# 160229_AriloRX_REV3_1_1.net
KiCad netlist of a schematic drawn in EAGLE
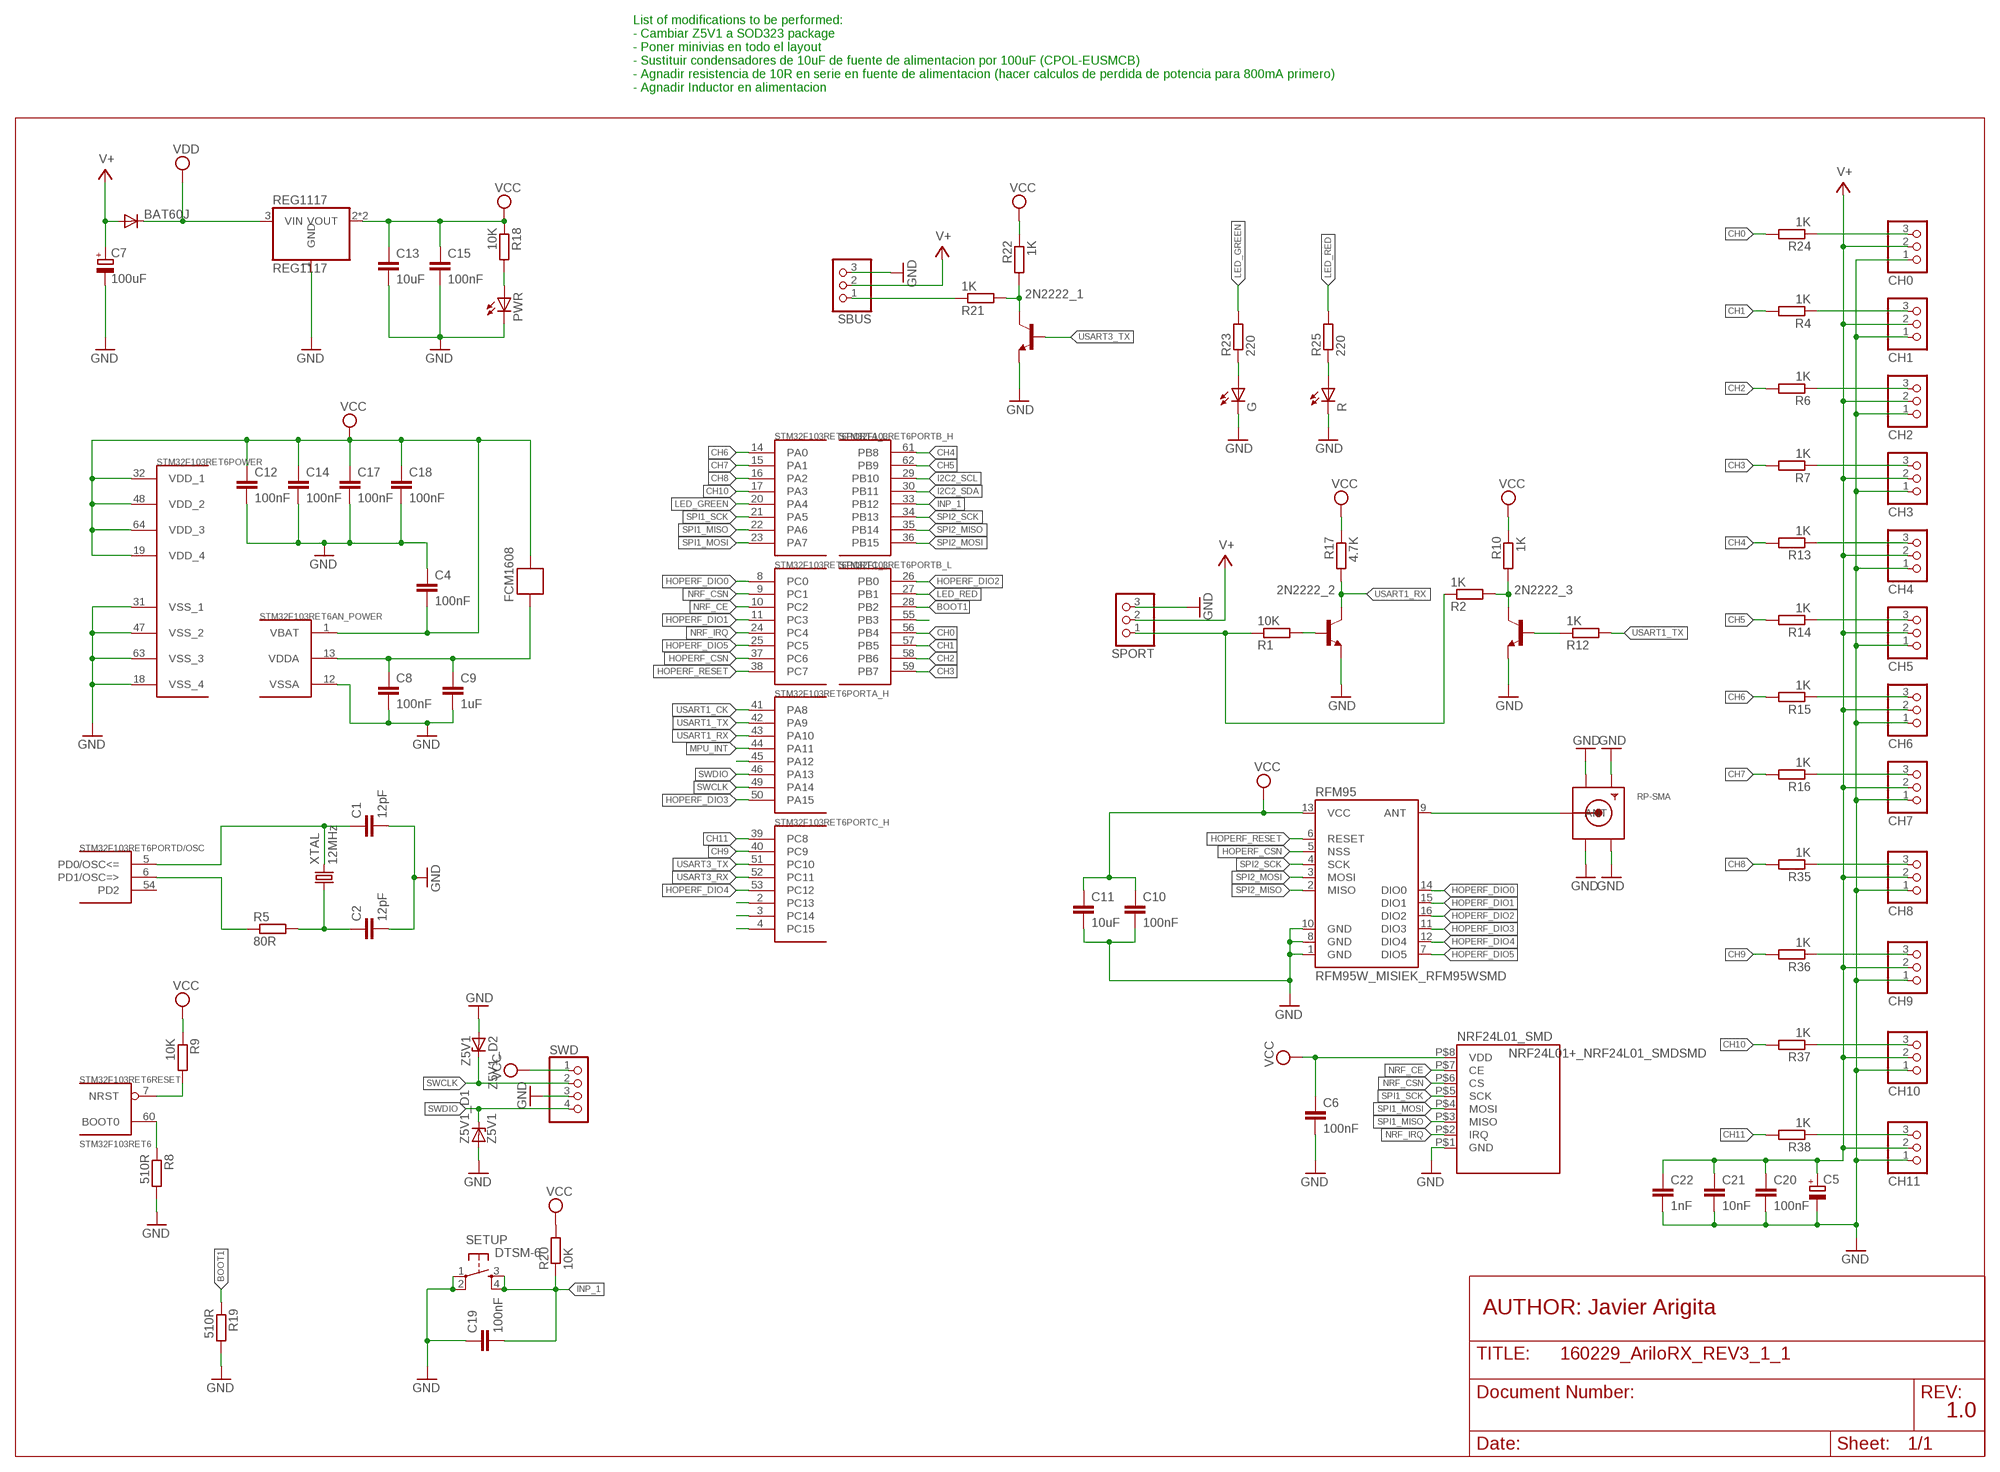
[diagram p0: schematic, sheet 1]

(export (version "E")
  (design (tool "Eeschema 10.0.6"))
  (components
    (comp (ref "2N2222_1")
      (value "MMBT2222ALT1-NPN-SOT23-BEC")
      (footprint "eagle-import:SOT23-BEC")
      (libsource (lib "eagle-import") (part "-NPN-SOT23-BECMMBT2222ALT1"))
    )
    (comp (ref "2N2222_2")
      (value "MMBT2222ALT1-NPN-SOT23-BEC")
      (footprint "eagle-import:SOT23-BEC")
      (libsource (lib "eagle-import") (part "-NPN-SOT23-BECMMBT2222ALT1"))
    )
    (comp (ref "2N2222_3")
      (value "MMBT2222ALT1-NPN-SOT23-BEC")
      (footprint "eagle-import:SOT23-BEC")
      (libsource (lib "eagle-import") (part "-NPN-SOT23-BECMMBT2222ALT1"))
    )
    (comp (ref "BAT60J")
      (value "DIODE-SOD323-R")
      (footprint "eagle-import:SOD323-R")
      (libsource (lib "eagle-import") (part "DIODE-SOD323-R"))
    )
    (comp (ref "C1")
      (value "12pF")
      (footprint "eagle-import:RESISTOR_C0603")
      (libsource (lib "eagle-import") (part "RESISTOR_C-EUC0603"))
    )
    (comp (ref "C2")
      (value "12pF")
      (footprint "eagle-import:RESISTOR_C0603")
      (libsource (lib "eagle-import") (part "RESISTOR_C-EUC0603"))
    )
    (comp (ref "C4")
      (value "100nF")
      (footprint "eagle-import:RESISTOR_C0603")
      (libsource (lib "eagle-import") (part "RESISTOR_C-EUC0603"))
    )
    (comp (ref "C5")
      (value "CPOL-EUSMCB")
      (footprint "eagle-import:SMC_B")
      (libsource (lib "eagle-import") (part "CPOL-EUSMCB"))
    )
    (comp (ref "C6")
      (value "100nF")
      (footprint "eagle-import:RESISTOR_C0603")
      (libsource (lib "eagle-import") (part "RESISTOR_C-EUC0603"))
    )
    (comp (ref "C7")
      (value "100uF")
      (footprint "eagle-import:SMC_B")
      (libsource (lib "eagle-import") (part "CPOL-EUSMCB"))
    )
    (comp (ref "C8")
      (value "100nF")
      (footprint "eagle-import:RESISTOR_C0603")
      (libsource (lib "eagle-import") (part "RESISTOR_C-EUC0603"))
    )
    (comp (ref "C9")
      (value "1uF")
      (footprint "eagle-import:RESISTOR_C0603")
      (libsource (lib "eagle-import") (part "RESISTOR_C-EUC0603"))
    )
    (comp (ref "C10")
      (value "100nF")
      (footprint "eagle-import:RESISTOR_C0603")
      (libsource (lib "eagle-import") (part "RESISTOR_C-EUC0603"))
    )
    (comp (ref "C11")
      (value "10uF")
      (footprint "eagle-import:RESISTOR_C3216")
      (libsource (lib "eagle-import") (part "RESISTOR_C-EUC3216"))
    )
    (comp (ref "C12")
      (value "100nF")
      (footprint "eagle-import:RESISTOR_C0603")
      (libsource (lib "eagle-import") (part "RESISTOR_C-EUC0603"))
    )
    (comp (ref "C13")
      (value "10uF")
      (footprint "eagle-import:RESISTOR_C3216")
      (libsource (lib "eagle-import") (part "RESISTOR_C-EUC3216"))
    )
    (comp (ref "C14")
      (value "100nF")
      (footprint "eagle-import:RESISTOR_C0603")
      (libsource (lib "eagle-import") (part "RESISTOR_C-EUC0603"))
    )
    (comp (ref "C15")
      (value "100nF")
      (footprint "eagle-import:RESISTOR_C0603")
      (libsource (lib "eagle-import") (part "RESISTOR_C-EUC0603"))
    )
    (comp (ref "C17")
      (value "100nF")
      (footprint "eagle-import:RESISTOR_C0603")
      (libsource (lib "eagle-import") (part "RESISTOR_C-EUC0603"))
    )
    (comp (ref "C18")
      (value "100nF")
      (footprint "eagle-import:RESISTOR_C0603")
      (libsource (lib "eagle-import") (part "RESISTOR_C-EUC0603"))
    )
    (comp (ref "C19")
      (value "100nF")
      (footprint "eagle-import:RESISTOR_C0603")
      (libsource (lib "eagle-import") (part "RESISTOR_C-EUC0603"))
    )
    (comp (ref "C20")
      (value "100nF")
      (footprint "eagle-import:RESISTOR_C0603")
      (libsource (lib "eagle-import") (part "RESISTOR_C-EUC0603"))
    )
    (comp (ref "C21")
      (value "10nF")
      (footprint "eagle-import:RESISTOR_C0603")
      (libsource (lib "eagle-import") (part "RESISTOR_C-EUC0603"))
    )
    (comp (ref "C22")
      (value "1nF")
      (footprint "eagle-import:RESISTOR_C0603")
      (libsource (lib "eagle-import") (part "RESISTOR_C-EUC0603"))
    )
    (comp (ref "CH0")
      (value "PINHD-1X3")
      (footprint "eagle-import:1X03")
      (libsource (lib "eagle-import") (part "PINHD-1X3"))
    )
    (comp (ref "CH1")
      (value "PINHD-1X3")
      (footprint "eagle-import:1X03")
      (libsource (lib "eagle-import") (part "PINHD-1X3"))
    )
    (comp (ref "CH2")
      (value "PINHD-1X3")
      (footprint "eagle-import:1X03")
      (libsource (lib "eagle-import") (part "PINHD-1X3"))
    )
    (comp (ref "CH3")
      (value "PINHD-1X3")
      (footprint "eagle-import:1X03")
      (libsource (lib "eagle-import") (part "PINHD-1X3"))
    )
    (comp (ref "CH4")
      (value "PINHD-1X3")
      (footprint "eagle-import:1X03")
      (libsource (lib "eagle-import") (part "PINHD-1X3"))
    )
    (comp (ref "CH5")
      (value "PINHD-1X3")
      (footprint "eagle-import:1X03")
      (libsource (lib "eagle-import") (part "PINHD-1X3"))
    )
    (comp (ref "CH6")
      (value "PINHD-1X3")
      (footprint "eagle-import:1X03")
      (libsource (lib "eagle-import") (part "PINHD-1X3"))
    )
    (comp (ref "CH7")
      (value "PINHD-1X3")
      (footprint "eagle-import:1X03")
      (libsource (lib "eagle-import") (part "PINHD-1X3"))
    )
    (comp (ref "CH8")
      (value "PINHD-1X3")
      (footprint "eagle-import:1X03")
      (libsource (lib "eagle-import") (part "PINHD-1X3"))
    )
    (comp (ref "CH9")
      (value "PINHD-1X3")
      (footprint "eagle-import:1X03")
      (libsource (lib "eagle-import") (part "PINHD-1X3"))
    )
    (comp (ref "CH10")
      (value "PINHD-1X3")
      (footprint "eagle-import:1X03")
      (libsource (lib "eagle-import") (part "PINHD-1X3"))
    )
    (comp (ref "CH11")
      (value "PINHD-1X3")
      (footprint "eagle-import:1X03")
      (libsource (lib "eagle-import") (part "PINHD-1X3"))
    )
    (comp (ref "FCM1608")
      (value "FERRITE-BEAD")
      (footprint "eagle-import:R0603")
      (libsource (lib "eagle-import") (part "FERRITE-BEAD"))
    )
    (comp (ref "G")
      (value "LEDCHIP-LED0603")
      (footprint "eagle-import:CHIP-LED0603")
      (libsource (lib "eagle-import") (part "LEDCHIP-LED0603"))
    )
    (comp (ref "NRF24L01_SMD")
      (value "NRF24L01+_NRF24L01_SMDSMD")
      (footprint "eagle-import:NRF24L01+_NRF24L01_SMD")
      (libsource (lib "eagle-import") (part "NRF24L01+_NRF24L01_SMDSMD"))
    )
    (comp (ref "PWR")
      (value "LED_LEDCHIP-LED0603")
      (footprint "eagle-import:LED_CHIP-LED0603")
      (libsource (lib "eagle-import") (part "LED_LEDCHIP-LED0603"))
    )
    (comp (ref "R")
      (value "LEDCHIP-LED0603")
      (footprint "eagle-import:CHIP-LED0603")
      (libsource (lib "eagle-import") (part "LEDCHIP-LED0603"))
    )
    (comp (ref "R1")
      (value "10K")
      (footprint "eagle-import:RCL_R0603")
      (libsource (lib "eagle-import") (part "RCL_R-EU_R0603"))
    )
    (comp (ref "R2")
      (value "1K")
      (footprint "eagle-import:RCL_R0603")
      (libsource (lib "eagle-import") (part "RCL_R-EU_R0603"))
    )
    (comp (ref "R4")
      (value "1K")
      (footprint "eagle-import:RCL_R0603")
      (libsource (lib "eagle-import") (part "RCL_R-EU_R0603"))
    )
    (comp (ref "R5")
      (value "80R")
      (footprint "eagle-import:RCL_R0603")
      (libsource (lib "eagle-import") (part "RCL_R-EU_R0603"))
    )
    (comp (ref "R6")
      (value "1K")
      (footprint "eagle-import:RCL_R0603")
      (libsource (lib "eagle-import") (part "RCL_R-EU_R0603"))
    )
    (comp (ref "R7")
      (value "1K")
      (footprint "eagle-import:RCL_R0603")
      (libsource (lib "eagle-import") (part "RCL_R-EU_R0603"))
    )
    (comp (ref "R8")
      (value "510R")
      (footprint "eagle-import:RCL_R0603")
      (libsource (lib "eagle-import") (part "RCL_R-EU_R0603"))
    )
    (comp (ref "R9")
      (value "10K")
      (footprint "eagle-import:RCL_R0603")
      (libsource (lib "eagle-import") (part "RCL_R-EU_R0603"))
    )
    (comp (ref "R10")
      (value "1K")
      (footprint "eagle-import:RCL_R0603")
      (libsource (lib "eagle-import") (part "RCL_R-EU_R0603"))
    )
    (comp (ref "R12")
      (value "1K")
      (footprint "eagle-import:RCL_R0603")
      (libsource (lib "eagle-import") (part "RCL_R-EU_R0603"))
    )
    (comp (ref "R13")
      (value "1K")
      (footprint "eagle-import:RCL_R0603")
      (libsource (lib "eagle-import") (part "RCL_R-EU_R0603"))
    )
    (comp (ref "R14")
      (value "1K")
      (footprint "eagle-import:RCL_R0603")
      (libsource (lib "eagle-import") (part "RCL_R-EU_R0603"))
    )
    (comp (ref "R15")
      (value "1K")
      (footprint "eagle-import:RCL_R0603")
      (libsource (lib "eagle-import") (part "RCL_R-EU_R0603"))
    )
    (comp (ref "R16")
      (value "1K")
      (footprint "eagle-import:RCL_R0603")
      (libsource (lib "eagle-import") (part "RCL_R-EU_R0603"))
    )
    (comp (ref "R17")
      (value "4.7K")
      (footprint "eagle-import:RCL_R0603")
      (libsource (lib "eagle-import") (part "RCL_R-EU_R0603"))
    )
    (comp (ref "R18")
      (value "10K")
      (footprint "eagle-import:RCL_R0603")
      (libsource (lib "eagle-import") (part "RCL_R-EU_R0603"))
    )
    (comp (ref "R19")
      (value "510R")
      (footprint "eagle-import:RCL_R0603")
      (libsource (lib "eagle-import") (part "RCL_R-EU_R0603"))
    )
    (comp (ref "R20")
      (value "10K")
      (footprint "eagle-import:RCL_R0603")
      (libsource (lib "eagle-import") (part "RCL_R-EU_R0603"))
    )
    (comp (ref "R21")
      (value "1K")
      (footprint "eagle-import:RCL_R0603")
      (libsource (lib "eagle-import") (part "RCL_R-EU_R0603"))
    )
    (comp (ref "R22")
      (value "1K")
      (footprint "eagle-import:RCL_R0603")
      (libsource (lib "eagle-import") (part "RCL_R-EU_R0603"))
    )
    (comp (ref "R23")
      (value "220")
      (footprint "eagle-import:RCL_R0603")
      (libsource (lib "eagle-import") (part "RCL_R-EU_R0603"))
    )
    (comp (ref "R24")
      (value "1K")
      (footprint "eagle-import:RCL_R0603")
      (libsource (lib "eagle-import") (part "RCL_R-EU_R0603"))
    )
    (comp (ref "R25")
      (value "220")
      (footprint "eagle-import:RCL_R0603")
      (libsource (lib "eagle-import") (part "RCL_R-EU_R0603"))
    )
    (comp (ref "R35")
      (value "1K")
      (footprint "eagle-import:RCL_R0603")
      (libsource (lib "eagle-import") (part "RCL_R-EU_R0603"))
    )
    (comp (ref "R36")
      (value "1K")
      (footprint "eagle-import:RCL_R0603")
      (libsource (lib "eagle-import") (part "RCL_R-EU_R0603"))
    )
    (comp (ref "R37")
      (value "1K")
      (footprint "eagle-import:RCL_R0603")
      (libsource (lib "eagle-import") (part "RCL_R-EU_R0603"))
    )
    (comp (ref "R38")
      (value "1K")
      (footprint "eagle-import:RCL_R0603")
      (libsource (lib "eagle-import") (part "RCL_R-EU_R0603"))
    )
    (comp (ref "REG1117")
      (value "REG1117")
      (footprint "eagle-import:SOT223")
      (libsource (lib "eagle-import") (part "REG1117"))
    )
    (comp (ref "RFM95")
      (value "RFM95W_MISIEK_RFM95WSMD")
      (footprint "eagle-import:RFM95W_MISIEK_RFM95W_SMD")
      (libsource (lib "eagle-import") (part "RFM95W_MISIEK_RFM95WSMD"))
    )
    (comp (ref "RP-SMA")
      (value "SMACONNECTOR_EDGE")
      (footprint "eagle-import:SMA_EDGELAUNCH")
      (libsource (lib "eagle-import") (part "SMACONNECTOR_EDGE"))
    )
    (comp (ref "SBUS")
      (value "PINHD-1X3")
      (footprint "eagle-import:1X03")
      (libsource (lib "eagle-import") (part "PINHD-1X3"))
    )
    (comp (ref "SETUP")
      (value "DTSM-6")
      (footprint "eagle-import:DTSM-6")
      (libsource (lib "eagle-import") (part "DTSM-6"))
    )
    (comp (ref "SPORT")
      (value "PINHD-1X3")
      (footprint "eagle-import:1X03")
      (libsource (lib "eagle-import") (part "PINHD-1X3"))
    )
    (comp (ref "STM32F103RET6")
      (value "STM32F103RET6")
      (footprint "eagle-import:TQFP64")
      (libsource (lib "eagle-import") (part "STM32F10XRXT6"))
    )
    (comp (ref "SWD")
      (value "PINHD-1X4")
      (footprint "eagle-import:1X04")
      (libsource (lib "eagle-import") (part "PINHD-1X4"))
    )
    (comp (ref "XTAL")
      (value "12MHz")
      (footprint "eagle-import:CRYSTAL-SMD-5X3")
      (libsource (lib "eagle-import") (part "CRYSTAL5X3"))
    )
    (comp (ref "Z5V1_D1")
      (value "Z5V1")
      (footprint "eagle-import:SOD80C")
      (libsource (lib "eagle-import") (part "ZENER-DIODESOD80C"))
    )
    (comp (ref "Z5V1_D2")
      (value "Z5V1")
      (footprint "eagle-import:SOD80C")
      (libsource (lib "eagle-import") (part "ZENER-DIODESOD80C"))
    )
  )
  (nets
    (net (code "1") (name "BOOT1") (class "Default")
      (node (ref "R19") (pin "1") (pinfunction "1_1") (pintype "passive"))
      (node (ref "STM32F103RET6") (pin "28") (pinfunction "PB2_28") (pintype "bidirectional"))
    )
    (net (code "2") (name "CH0") (class "Default")
      (node (ref "R24") (pin "2") (pinfunction "2_2") (pintype "passive"))
      (node (ref "STM32F103RET6") (pin "56") (pinfunction "PB4_56") (pintype "bidirectional"))
    )
    (net (code "3") (name "CH1") (class "Default")
      (node (ref "R4") (pin "2") (pinfunction "2_2") (pintype "passive"))
      (node (ref "STM32F103RET6") (pin "57") (pinfunction "PB5_57") (pintype "bidirectional"))
    )
    (net (code "4") (name "CH2") (class "Default")
      (node (ref "R6") (pin "2") (pinfunction "2_2") (pintype "passive"))
      (node (ref "STM32F103RET6") (pin "58") (pinfunction "PB6_58") (pintype "bidirectional"))
    )
    (net (code "5") (name "CH3") (class "Default")
      (node (ref "R7") (pin "2") (pinfunction "2_2") (pintype "passive"))
      (node (ref "STM32F103RET6") (pin "59") (pinfunction "PB7_59") (pintype "bidirectional"))
    )
    (net (code "6") (name "CH4") (class "Default")
      (node (ref "R13") (pin "2") (pinfunction "2_2") (pintype "passive"))
      (node (ref "STM32F103RET6") (pin "61") (pinfunction "PB8_61") (pintype "bidirectional"))
    )
    (net (code "7") (name "CH5") (class "Default")
      (node (ref "R14") (pin "2") (pinfunction "2_2") (pintype "passive"))
      (node (ref "STM32F103RET6") (pin "62") (pinfunction "PB9_62") (pintype "bidirectional"))
    )
    (net (code "8") (name "CH6") (class "Default")
      (node (ref "R15") (pin "2") (pinfunction "2_2") (pintype "passive"))
      (node (ref "STM32F103RET6") (pin "14") (pinfunction "PA0_14") (pintype "bidirectional"))
    )
    (net (code "9") (name "CH7") (class "Default")
      (node (ref "R16") (pin "2") (pinfunction "2_2") (pintype "passive"))
      (node (ref "STM32F103RET6") (pin "15") (pinfunction "PA1_15") (pintype "bidirectional"))
    )
    (net (code "10") (name "CH8") (class "Default")
      (node (ref "R35") (pin "2") (pinfunction "2_2") (pintype "passive"))
      (node (ref "STM32F103RET6") (pin "16") (pinfunction "PA2_16") (pintype "bidirectional"))
    )
    (net (code "11") (name "CH9") (class "Default")
      (node (ref "R36") (pin "2") (pinfunction "2_2") (pintype "passive"))
      (node (ref "STM32F103RET6") (pin "40") (pinfunction "PC9_40") (pintype "bidirectional"))
    )
    (net (code "12") (name "CH10") (class "Default")
      (node (ref "R37") (pin "2") (pinfunction "2_2") (pintype "passive"))
      (node (ref "STM32F103RET6") (pin "17") (pinfunction "PA3_17") (pintype "bidirectional"))
    )
    (net (code "13") (name "CH11") (class "Default")
      (node (ref "R38") (pin "2") (pinfunction "2_2") (pintype "passive"))
      (node (ref "STM32F103RET6") (pin "39") (pinfunction "PC8_39") (pintype "bidirectional"))
    )
    (net (code "14") (name "GND") (class "Default")
      (node (ref "2N2222_1") (pin "E") (pinfunction "E_E") (pintype "passive"))
      (node (ref "2N2222_2") (pin "E") (pinfunction "E_E") (pintype "passive"))
      (node (ref "2N2222_3") (pin "E") (pinfunction "E_E") (pintype "passive"))
      (node (ref "C1") (pin "2") (pinfunction "2_2") (pintype "passive"))
      (node (ref "C10") (pin "2") (pinfunction "2_2") (pintype "passive"))
      (node (ref "C11") (pin "2") (pinfunction "2_2") (pintype "passive"))
      (node (ref "C12") (pin "2") (pinfunction "2_2") (pintype "passive"))
      (node (ref "C13") (pin "2") (pinfunction "2_2") (pintype "passive"))
      (node (ref "C14") (pin "2") (pinfunction "2_2") (pintype "passive"))
      (node (ref "C15") (pin "2") (pinfunction "2_2") (pintype "passive"))
      (node (ref "C17") (pin "2") (pinfunction "2_2") (pintype "passive"))
      (node (ref "C18") (pin "2") (pinfunction "2_2") (pintype "passive"))
      (node (ref "C19") (pin "1") (pinfunction "1_1") (pintype "passive"))
      (node (ref "C2") (pin "2") (pinfunction "2_2") (pintype "passive"))
      (node (ref "C20") (pin "2") (pinfunction "2_2") (pintype "passive"))
      (node (ref "C21") (pin "2") (pinfunction "2_2") (pintype "passive"))
      (node (ref "C22") (pin "2") (pinfunction "2_2") (pintype "passive"))
      (node (ref "C4") (pin "1") (pinfunction "1_1") (pintype "passive"))
      (node (ref "C5") (pin "-") (pinfunction "-_-") (pintype "passive"))
      (node (ref "C6") (pin "2") (pinfunction "2_2") (pintype "passive"))
      (node (ref "C7") (pin "-") (pinfunction "-_-") (pintype "passive"))
      (node (ref "C8") (pin "2") (pinfunction "2_2") (pintype "passive"))
      (node (ref "C9") (pin "2") (pinfunction "2_2") (pintype "passive"))
      (node (ref "CH0") (pin "1") (pinfunction "1_1") (pintype "passive"))
      (node (ref "CH1") (pin "1") (pinfunction "1_1") (pintype "passive"))
      (node (ref "CH10") (pin "1") (pinfunction "1_1") (pintype "passive"))
      (node (ref "CH11") (pin "1") (pinfunction "1_1") (pintype "passive"))
      (node (ref "CH2") (pin "1") (pinfunction "1_1") (pintype "passive"))
      (node (ref "CH3") (pin "1") (pinfunction "1_1") (pintype "passive"))
      (node (ref "CH4") (pin "1") (pinfunction "1_1") (pintype "passive"))
      (node (ref "CH5") (pin "1") (pinfunction "1_1") (pintype "passive"))
      (node (ref "CH6") (pin "1") (pinfunction "1_1") (pintype "passive"))
      (node (ref "CH7") (pin "1") (pinfunction "1_1") (pintype "passive"))
      (node (ref "CH8") (pin "1") (pinfunction "1_1") (pintype "passive"))
      (node (ref "CH9") (pin "1") (pinfunction "1_1") (pintype "passive"))
      (node (ref "G") (pin "C") (pinfunction "C_C") (pintype "passive"))
      (node (ref "NRF24L01_SMD") (pin "P$1") (pinfunction "GND_P$1") (pintype "power_in"))
      (node (ref "PWR") (pin "C") (pinfunction "C_C") (pintype "passive"))
      (node (ref "R") (pin "C") (pinfunction "C_C") (pintype "passive"))
      (node (ref "R19") (pin "2") (pinfunction "2_2") (pintype "passive"))
      (node (ref "R8") (pin "2") (pinfunction "2_2") (pintype "passive"))
      (node (ref "REG1117") (pin "1") (pinfunction "GND_1") (pintype "power_in"))
      (node (ref "RFM95") (pin "1") (pinfunction "GND_1") (pintype "power_in"))
      (node (ref "RFM95") (pin "10") (pinfunction "GND_10") (pintype "power_in"))
      (node (ref "RFM95") (pin "8") (pinfunction "GND_8") (pintype "power_in"))
      (node (ref "RP-SMA") (pin "GND@1") (pinfunction "GND4_GND@1") (pintype "power_in"))
      (node (ref "RP-SMA") (pin "GND@2") (pinfunction "GND3_GND@2") (pintype "power_in"))
      (node (ref "RP-SMA") (pin "GND@3") (pinfunction "GND2_GND@3") (pintype "power_in"))
      (node (ref "RP-SMA") (pin "GND@4") (pinfunction "GND1_GND@4") (pintype "power_in"))
      (node (ref "SBUS") (pin "3") (pinfunction "3_3") (pintype "passive"))
      (node (ref "SETUP") (pin "1") (pinfunction "1_1") (pintype "passive"))
      (node (ref "SETUP") (pin "2") (pinfunction "2_2") (pintype "passive"))
      (node (ref "SPORT") (pin "3") (pinfunction "3_3") (pintype "passive"))
      (node (ref "STM32F103RET6") (pin "12") (pinfunction "VSSA_12") (pintype "power_in"))
      (node (ref "STM32F103RET6") (pin "18") (pinfunction "VSS_4_18") (pintype "power_in"))
      (node (ref "STM32F103RET6") (pin "31") (pinfunction "VSS_1_31") (pintype "power_in"))
      (node (ref "STM32F103RET6") (pin "47") (pinfunction "VSS_2_47") (pintype "power_in"))
      (node (ref "STM32F103RET6") (pin "63") (pinfunction "VSS_3_63") (pintype "power_in"))
      (node (ref "SWD") (pin "3") (pinfunction "3_3") (pintype "passive"))
      (node (ref "Z5V1_D1") (pin "A") (pinfunction "A_A") (pintype "passive"))
      (node (ref "Z5V1_D2") (pin "A") (pinfunction "A_A") (pintype "passive"))
    )
    (net (code "15") (name "HOPERF_CSN") (class "Default")
      (node (ref "RFM95") (pin "5") (pinfunction "NSS_5") (pintype "input"))
      (node (ref "STM32F103RET6") (pin "37") (pinfunction "PC6_37") (pintype "bidirectional"))
    )
    (net (code "16") (name "HOPERF_DIO0") (class "Default")
      (node (ref "RFM95") (pin "14") (pinfunction "DIO0_14") (pintype "input"))
      (node (ref "STM32F103RET6") (pin "8") (pinfunction "PC0_8") (pintype "bidirectional"))
    )
    (net (code "17") (name "HOPERF_DIO1") (class "Default")
      (node (ref "RFM95") (pin "15") (pinfunction "DIO1_15") (pintype "input"))
      (node (ref "STM32F103RET6") (pin "11") (pinfunction "PC3_11") (pintype "bidirectional"))
    )
    (net (code "18") (name "HOPERF_DIO2") (class "Default")
      (node (ref "RFM95") (pin "16") (pinfunction "DIO2_16") (pintype "input"))
      (node (ref "STM32F103RET6") (pin "26") (pinfunction "PB0_26") (pintype "bidirectional"))
    )
    (net (code "19") (name "HOPERF_DIO3") (class "Default")
      (node (ref "RFM95") (pin "11") (pinfunction "DIO3_11") (pintype "bidirectional"))
      (node (ref "STM32F103RET6") (pin "50") (pinfunction "PA15_50") (pintype "bidirectional"))
    )
    (net (code "20") (name "HOPERF_DIO4") (class "Default")
      (node (ref "RFM95") (pin "12") (pinfunction "DIO4_12") (pintype "bidirectional"))
      (node (ref "STM32F103RET6") (pin "53") (pinfunction "PC12_53") (pintype "bidirectional"))
    )
    (net (code "21") (name "HOPERF_DIO5") (class "Default")
      (node (ref "RFM95") (pin "7") (pinfunction "DIO5_7") (pintype "bidirectional"))
      (node (ref "STM32F103RET6") (pin "25") (pinfunction "PC5_25") (pintype "bidirectional"))
    )
    (net (code "22") (name "HOPERF_RESET") (class "Default")
      (node (ref "RFM95") (pin "6") (pinfunction "RESET_6") (pintype "output"))
      (node (ref "STM32F103RET6") (pin "38") (pinfunction "PC7_38") (pintype "bidirectional"))
    )
    (net (code "23") (name "I2C2_SCL") (class "Default")
      (node (ref "STM32F103RET6") (pin "29") (pinfunction "PB10_29") (pintype "bidirectional"))
    )
    (net (code "24") (name "I2C2_SDA") (class "Default")
      (node (ref "STM32F103RET6") (pin "30") (pinfunction "PB11_30") (pintype "bidirectional"))
    )
    (net (code "25") (name "INP_1") (class "Default")
      (node (ref "C19") (pin "2") (pinfunction "2_2") (pintype "passive"))
      (node (ref "R20") (pin "1") (pinfunction "1_1") (pintype "passive"))
      (node (ref "SETUP") (pin "3") (pinfunction "3_3") (pintype "passive"))
      (node (ref "SETUP") (pin "4") (pinfunction "4_4") (pintype "passive"))
      (node (ref "STM32F103RET6") (pin "33") (pinfunction "PB12_33") (pintype "bidirectional"))
    )
    (net (code "26") (name "LED_GREEN") (class "Default")
      (node (ref "R23") (pin "2") (pinfunction "2_2") (pintype "passive"))
      (node (ref "STM32F103RET6") (pin "20") (pinfunction "PA4_20") (pintype "bidirectional"))
    )
    (net (code "27") (name "LED_RED") (class "Default")
      (node (ref "R25") (pin "2") (pinfunction "2_2") (pintype "passive"))
      (node (ref "STM32F103RET6") (pin "27") (pinfunction "PB1_27") (pintype "bidirectional"))
    )
    (net (code "28") (name "MPU_INT") (class "Default")
      (node (ref "STM32F103RET6") (pin "44") (pinfunction "PA11_44") (pintype "bidirectional"))
    )
    (net (code "29") (name "NRF_CE") (class "Default")
      (node (ref "NRF24L01_SMD") (pin "P$7") (pinfunction "CE_P$7") (pintype "input"))
      (node (ref "STM32F103RET6") (pin "10") (pinfunction "PC2_10") (pintype "bidirectional"))
    )
    (net (code "30") (name "NRF_CSN") (class "Default")
      (node (ref "NRF24L01_SMD") (pin "P$6") (pinfunction "CS_P$6") (pintype "input"))
      (node (ref "STM32F103RET6") (pin "9") (pinfunction "PC1_9") (pintype "bidirectional"))
    )
    (net (code "31") (name "NRF_IRQ") (class "Default")
      (node (ref "NRF24L01_SMD") (pin "P$2") (pinfunction "IRQ_P$2") (pintype "output"))
      (node (ref "STM32F103RET6") (pin "24") (pinfunction "PC4_24") (pintype "bidirectional"))
    )
    (net (code "32") (name "Net-(2N2222_1-PadC)") (class "Default")
      (node (ref "2N2222_1") (pin "C") (pinfunction "C_C") (pintype "passive"))
      (node (ref "R21") (pin "2") (pinfunction "2_2") (pintype "passive"))
      (node (ref "R22") (pin "2") (pinfunction "2_2") (pintype "passive"))
    )
    (net (code "33") (name "Net-(2N2222_2-PadB)") (class "Default")
      (node (ref "2N2222_2") (pin "B") (pinfunction "B_B") (pintype "passive"))
      (node (ref "R1") (pin "2") (pinfunction "2_2") (pintype "passive"))
    )
    (net (code "34") (name "Net-(2N2222_3-PadB)") (class "Default")
      (node (ref "2N2222_3") (pin "B") (pinfunction "B_B") (pintype "passive"))
      (node (ref "R12") (pin "1") (pinfunction "1_1") (pintype "passive"))
    )
    (net (code "35") (name "Net-(2N2222_3-PadC)") (class "Default")
      (node (ref "2N2222_3") (pin "C") (pinfunction "C_C") (pintype "passive"))
      (node (ref "R10") (pin "2") (pinfunction "2_2") (pintype "passive"))
      (node (ref "R2") (pin "2") (pinfunction "2_2") (pintype "passive"))
    )
    (net (code "36") (name "Net-(C2-Pad1)") (class "Default")
      (node (ref "C2") (pin "1") (pinfunction "1_1") (pintype "passive"))
      (node (ref "R5") (pin "2") (pinfunction "2_2") (pintype "passive"))
      (node (ref "XTAL") (pin "1") (pinfunction "1_1") (pintype "passive"))
    )
    (net (code "37") (name "Net-(CH0-Pad3)") (class "Default")
      (node (ref "CH0") (pin "3") (pinfunction "3_3") (pintype "passive"))
      (node (ref "R24") (pin "1") (pinfunction "1_1") (pintype "passive"))
    )
    (net (code "38") (name "Net-(CH1-Pad3)") (class "Default")
      (node (ref "CH1") (pin "3") (pinfunction "3_3") (pintype "passive"))
      (node (ref "R4") (pin "1") (pinfunction "1_1") (pintype "passive"))
    )
    (net (code "39") (name "Net-(CH2-Pad3)") (class "Default")
      (node (ref "CH2") (pin "3") (pinfunction "3_3") (pintype "passive"))
      (node (ref "R6") (pin "1") (pinfunction "1_1") (pintype "passive"))
    )
    (net (code "40") (name "Net-(CH3-Pad3)") (class "Default")
      (node (ref "CH3") (pin "3") (pinfunction "3_3") (pintype "passive"))
      (node (ref "R7") (pin "1") (pinfunction "1_1") (pintype "passive"))
    )
    (net (code "41") (name "Net-(CH4-Pad3)") (class "Default")
      (node (ref "CH4") (pin "3") (pinfunction "3_3") (pintype "passive"))
      (node (ref "R13") (pin "1") (pinfunction "1_1") (pintype "passive"))
    )
    (net (code "42") (name "Net-(CH5-Pad3)") (class "Default")
      (node (ref "CH5") (pin "3") (pinfunction "3_3") (pintype "passive"))
      (node (ref "R14") (pin "1") (pinfunction "1_1") (pintype "passive"))
    )
    (net (code "43") (name "Net-(CH6-Pad3)") (class "Default")
      (node (ref "CH6") (pin "3") (pinfunction "3_3") (pintype "passive"))
      (node (ref "R15") (pin "1") (pinfunction "1_1") (pintype "passive"))
    )
    (net (code "44") (name "Net-(CH7-Pad3)") (class "Default")
      (node (ref "CH7") (pin "3") (pinfunction "3_3") (pintype "passive"))
      (node (ref "R16") (pin "1") (pinfunction "1_1") (pintype "passive"))
    )
    (net (code "45") (name "Net-(CH8-Pad3)") (class "Default")
      (node (ref "CH8") (pin "3") (pinfunction "3_3") (pintype "passive"))
      (node (ref "R35") (pin "1") (pinfunction "1_1") (pintype "passive"))
    )
    (net (code "46") (name "Net-(CH9-Pad3)") (class "Default")
      (node (ref "CH9") (pin "3") (pinfunction "3_3") (pintype "passive"))
      (node (ref "R36") (pin "1") (pinfunction "1_1") (pintype "passive"))
    )
    (net (code "47") (name "Net-(CH10-Pad3)") (class "Default")
      (node (ref "CH10") (pin "3") (pinfunction "3_3") (pintype "passive"))
      (node (ref "R37") (pin "1") (pinfunction "1_1") (pintype "passive"))
    )
    (net (code "48") (name "Net-(CH11-Pad3)") (class "Default")
      (node (ref "CH11") (pin "3") (pinfunction "3_3") (pintype "passive"))
      (node (ref "R38") (pin "1") (pinfunction "1_1") (pintype "passive"))
    )
    (net (code "49") (name "Net-(FCM1608-P$2)") (class "Default")
      (node (ref "C8") (pin "1") (pinfunction "1_1") (pintype "passive"))
      (node (ref "C9") (pin "1") (pinfunction "1_1") (pintype "passive"))
      (node (ref "FCM1608") (pin "2") (pinfunction "P$2_2") (pintype "bidirectional"))
      (node (ref "STM32F103RET6") (pin "13") (pinfunction "VDDA_13") (pintype "power_in"))
    )
    (net (code "50") (name "Net-(G-PadA)") (class "Default")
      (node (ref "G") (pin "A") (pinfunction "A_A") (pintype "passive"))
      (node (ref "R23") (pin "1") (pinfunction "1_1") (pintype "passive"))
    )
    (net (code "51") (name "Net-(PWR-PadA)") (class "Default")
      (node (ref "PWR") (pin "A") (pinfunction "A_A") (pintype "passive"))
      (node (ref "R18") (pin "2") (pinfunction "2_2") (pintype "passive"))
    )
    (net (code "52") (name "Net-(R-PadA)") (class "Default")
      (node (ref "R") (pin "A") (pinfunction "A_A") (pintype "passive"))
      (node (ref "R25") (pin "1") (pinfunction "1_1") (pintype "passive"))
    )
    (net (code "53") (name "Net-(R1-Pad1)") (class "Default")
      (node (ref "R1") (pin "1") (pinfunction "1_1") (pintype "passive"))
      (node (ref "R2") (pin "1") (pinfunction "1_1") (pintype "passive"))
      (node (ref "SPORT") (pin "1") (pinfunction "1_1") (pintype "passive"))
    )
    (net (code "54") (name "Net-(R21-Pad1)") (class "Default")
      (node (ref "R21") (pin "1") (pinfunction "1_1") (pintype "passive"))
      (node (ref "SBUS") (pin "1") (pinfunction "1_1") (pintype "passive"))
    )
    (net (code "55") (name "Net-(RFM95-ANT)") (class "Default")
      (node (ref "RFM95") (pin "9") (pinfunction "ANT_9") (pintype "bidirectional"))
      (node (ref "RP-SMA") (pin "P") (pinfunction "ANT_P") (pintype "bidirectional"))
    )
    (net (code "56") (name "Net-(STM32F103RET6H-PD0{slash}OSC<=)") (class "Default")
      (node (ref "C1") (pin "1") (pinfunction "1_1") (pintype "passive"))
      (node (ref "STM32F103RET6") (pin "5") (pinfunction "PD0/OSC<=_5") (pintype "bidirectional"))
      (node (ref "XTAL") (pin "3") (pinfunction "2_3") (pintype "passive"))
    )
    (net (code "57") (name "Net-(STM32F103RET6H-PD1{slash}OSC=>)") (class "Default")
      (node (ref "R5") (pin "1") (pinfunction "1_1") (pintype "passive"))
      (node (ref "STM32F103RET6") (pin "6") (pinfunction "PD1/OSC=>_6") (pintype "bidirectional"))
    )
    (net (code "58") (name "Net-(STM32F103RET6J-BOOT0)") (class "Default")
      (node (ref "R8") (pin "1") (pinfunction "1_1") (pintype "passive"))
      (node (ref "STM32F103RET6") (pin "60") (pinfunction "BOOT0_60") (pintype "input"))
    )
    (net (code "59") (name "Net-(STM32F103RET6J-NRST)") (class "Default")
      (node (ref "R9") (pin "2") (pinfunction "2_2") (pintype "passive"))
      (node (ref "STM32F103RET6") (pin "7") (pinfunction "NRST_7") (pintype "input"))
    )
    (net (code "60") (name "SPI1_MISO") (class "Default")
      (node (ref "NRF24L01_SMD") (pin "P$3") (pinfunction "MISO_P$3") (pintype "output"))
      (node (ref "STM32F103RET6") (pin "22") (pinfunction "PA6_22") (pintype "bidirectional"))
    )
    (net (code "61") (name "SPI1_MOSI") (class "Default")
      (node (ref "NRF24L01_SMD") (pin "P$4") (pinfunction "MOSI_P$4") (pintype "input"))
      (node (ref "STM32F103RET6") (pin "23") (pinfunction "PA7_23") (pintype "bidirectional"))
    )
    (net (code "62") (name "SPI1_SCK") (class "Default")
      (node (ref "NRF24L01_SMD") (pin "P$5") (pinfunction "SCK_P$5") (pintype "input"))
      (node (ref "STM32F103RET6") (pin "21") (pinfunction "PA5_21") (pintype "bidirectional"))
    )
    (net (code "63") (name "SPI2_MISO") (class "Default")
      (node (ref "RFM95") (pin "2") (pinfunction "MISO_2") (pintype "output"))
      (node (ref "STM32F103RET6") (pin "35") (pinfunction "PB14_35") (pintype "bidirectional"))
    )
    (net (code "64") (name "SPI2_MOSI") (class "Default")
      (node (ref "RFM95") (pin "3") (pinfunction "MOSI_3") (pintype "input"))
      (node (ref "STM32F103RET6") (pin "36") (pinfunction "PB15_36") (pintype "bidirectional"))
    )
    (net (code "65") (name "SPI2_SCK") (class "Default")
      (node (ref "RFM95") (pin "4") (pinfunction "SCK_4") (pintype "input"))
      (node (ref "STM32F103RET6") (pin "34") (pinfunction "PB13_34") (pintype "bidirectional"))
    )
    (net (code "66") (name "SWCLK") (class "Default")
      (node (ref "STM32F103RET6") (pin "49") (pinfunction "PA14_49") (pintype "bidirectional"))
      (node (ref "SWD") (pin "2") (pinfunction "2_2") (pintype "passive"))
      (node (ref "Z5V1_D2") (pin "C") (pinfunction "C_C") (pintype "passive"))
    )
    (net (code "67") (name "SWDIO") (class "Default")
      (node (ref "STM32F103RET6") (pin "46") (pinfunction "PA13_46") (pintype "bidirectional"))
      (node (ref "SWD") (pin "4") (pinfunction "4_4") (pintype "passive"))
      (node (ref "Z5V1_D1") (pin "C") (pinfunction "C_C") (pintype "passive"))
    )
    (net (code "68") (name "USART1_CK") (class "Default")
      (node (ref "STM32F103RET6") (pin "41") (pinfunction "PA8_41") (pintype "bidirectional"))
    )
    (net (code "69") (name "USART1_RX") (class "Default")
      (node (ref "2N2222_2") (pin "C") (pinfunction "C_C") (pintype "passive"))
      (node (ref "R17") (pin "2") (pinfunction "2_2") (pintype "passive"))
      (node (ref "STM32F103RET6") (pin "43") (pinfunction "PA10_43") (pintype "bidirectional"))
    )
    (net (code "70") (name "USART1_TX") (class "Default")
      (node (ref "R12") (pin "2") (pinfunction "2_2") (pintype "passive"))
      (node (ref "STM32F103RET6") (pin "42") (pinfunction "PA9_42") (pintype "bidirectional"))
    )
    (net (code "71") (name "USART3_RX") (class "Default")
      (node (ref "STM32F103RET6") (pin "52") (pinfunction "PC11_52") (pintype "bidirectional"))
    )
    (net (code "72") (name "USART3_TX") (class "Default")
      (node (ref "2N2222_1") (pin "B") (pinfunction "B_B") (pintype "passive"))
      (node (ref "STM32F103RET6") (pin "51") (pinfunction "PC10_51") (pintype "bidirectional"))
    )
    (net (code "73") (name "V+") (class "Default")
      (node (ref "BAT60J") (pin "A") (pinfunction "A_A") (pintype "passive"))
      (node (ref "C20") (pin "1") (pinfunction "1_1") (pintype "passive"))
      (node (ref "C21") (pin "1") (pinfunction "1_1") (pintype "passive"))
      (node (ref "C22") (pin "1") (pinfunction "1_1") (pintype "passive"))
      (node (ref "C5") (pin "+") (pinfunction "+_+") (pintype "passive"))
      (node (ref "C7") (pin "+") (pinfunction "+_+") (pintype "passive"))
      (node (ref "CH0") (pin "2") (pinfunction "2_2") (pintype "passive"))
      (node (ref "CH1") (pin "2") (pinfunction "2_2") (pintype "passive"))
      (node (ref "CH10") (pin "2") (pinfunction "2_2") (pintype "passive"))
      (node (ref "CH11") (pin "2") (pinfunction "2_2") (pintype "passive"))
      (node (ref "CH2") (pin "2") (pinfunction "2_2") (pintype "passive"))
      (node (ref "CH3") (pin "2") (pinfunction "2_2") (pintype "passive"))
      (node (ref "CH4") (pin "2") (pinfunction "2_2") (pintype "passive"))
      (node (ref "CH5") (pin "2") (pinfunction "2_2") (pintype "passive"))
      (node (ref "CH6") (pin "2") (pinfunction "2_2") (pintype "passive"))
      (node (ref "CH7") (pin "2") (pinfunction "2_2") (pintype "passive"))
      (node (ref "CH8") (pin "2") (pinfunction "2_2") (pintype "passive"))
      (node (ref "CH9") (pin "2") (pinfunction "2_2") (pintype "passive"))
      (node (ref "SBUS") (pin "2") (pinfunction "2_2") (pintype "passive"))
      (node (ref "SPORT") (pin "2") (pinfunction "2_2") (pintype "passive"))
    )
    (net (code "74") (name "VCC") (class "Default")
      (node (ref "C10") (pin "1") (pinfunction "1_1") (pintype "passive"))
      (node (ref "C11") (pin "1") (pinfunction "1_1") (pintype "passive"))
      (node (ref "C12") (pin "1") (pinfunction "1_1") (pintype "passive"))
      (node (ref "C13") (pin "1") (pinfunction "1_1") (pintype "passive"))
      (node (ref "C14") (pin "1") (pinfunction "1_1") (pintype "passive"))
      (node (ref "C15") (pin "1") (pinfunction "1_1") (pintype "passive"))
      (node (ref "C17") (pin "1") (pinfunction "1_1") (pintype "passive"))
      (node (ref "C18") (pin "1") (pinfunction "1_1") (pintype "passive"))
      (node (ref "C4") (pin "2") (pinfunction "2_2") (pintype "passive"))
      (node (ref "C6") (pin "1") (pinfunction "1_1") (pintype "passive"))
      (node (ref "FCM1608") (pin "1") (pinfunction "P$1_1") (pintype "bidirectional"))
      (node (ref "NRF24L01_SMD") (pin "P$8") (pinfunction "VDD_P$8") (pintype "bidirectional"))
      (node (ref "R10") (pin "1") (pinfunction "1_1") (pintype "passive"))
      (node (ref "R17") (pin "1") (pinfunction "1_1") (pintype "passive"))
      (node (ref "R18") (pin "1") (pinfunction "1_1") (pintype "passive"))
      (node (ref "R20") (pin "2") (pinfunction "2_2") (pintype "passive"))
      (node (ref "R22") (pin "1") (pinfunction "1_1") (pintype "passive"))
      (node (ref "R9") (pin "1") (pinfunction "1_1") (pintype "passive"))
      (node (ref "REG1117") (pin "2") (pinfunction "VOUT_2") (pintype "power_in"))
      (node (ref "REG1117") (pin "4") (pinfunction "VOUT_4") (pintype "power_in"))
      (node (ref "RFM95") (pin "13") (pinfunction "VCC_13") (pintype "bidirectional"))
      (node (ref "STM32F103RET6") (pin "1") (pinfunction "VBAT_1") (pintype "power_in"))
      (node (ref "STM32F103RET6") (pin "19") (pinfunction "VDD_4_19") (pintype "power_in"))
      (node (ref "STM32F103RET6") (pin "32") (pinfunction "VDD_1_32") (pintype "power_in"))
      (node (ref "STM32F103RET6") (pin "48") (pinfunction "VDD_2_48") (pintype "power_in"))
      (node (ref "STM32F103RET6") (pin "64") (pinfunction "VDD_3_64") (pintype "power_in"))
      (node (ref "SWD") (pin "1") (pinfunction "1_1") (pintype "passive"))
    )
    (net (code "75") (name "VDD") (class "Default")
      (node (ref "BAT60J") (pin "C") (pinfunction "C_C") (pintype "passive"))
      (node (ref "REG1117") (pin "3") (pinfunction "VIN_3") (pintype "input"))
    )
    (net (code "76") (name "unconnected-(STM32F103RET6B-PA12-Pad45)") (class "Default")
      (node (ref "STM32F103RET6") (pin "45") (pinfunction "PA12_45") (pintype "bidirectional"))
    )
    (net (code "77") (name "unconnected-(STM32F103RET6E-PB3-Pad55)") (class "Default")
      (node (ref "STM32F103RET6") (pin "55") (pinfunction "PB3_55") (pintype "bidirectional"))
    )
    (net (code "78") (name "unconnected-(STM32F103RET6F-PC13-Pad2)") (class "Default")
      (node (ref "STM32F103RET6") (pin "2") (pinfunction "PC13_2") (pintype "bidirectional"))
    )
    (net (code "79") (name "unconnected-(STM32F103RET6F-PC14-Pad3)") (class "Default")
      (node (ref "STM32F103RET6") (pin "3") (pinfunction "PC14_3") (pintype "bidirectional"))
    )
    (net (code "80") (name "unconnected-(STM32F103RET6F-PC15-Pad4)") (class "Default")
      (node (ref "STM32F103RET6") (pin "4") (pinfunction "PC15_4") (pintype "bidirectional"))
    )
    (net (code "81") (name "unconnected-(STM32F103RET6H-PD2-Pad54)") (class "Default")
      (node (ref "STM32F103RET6") (pin "54") (pinfunction "PD2_54") (pintype "bidirectional"))
    )
  )
)
